# alt.net
KiCad netlist of a schematic drawn in EAGLE
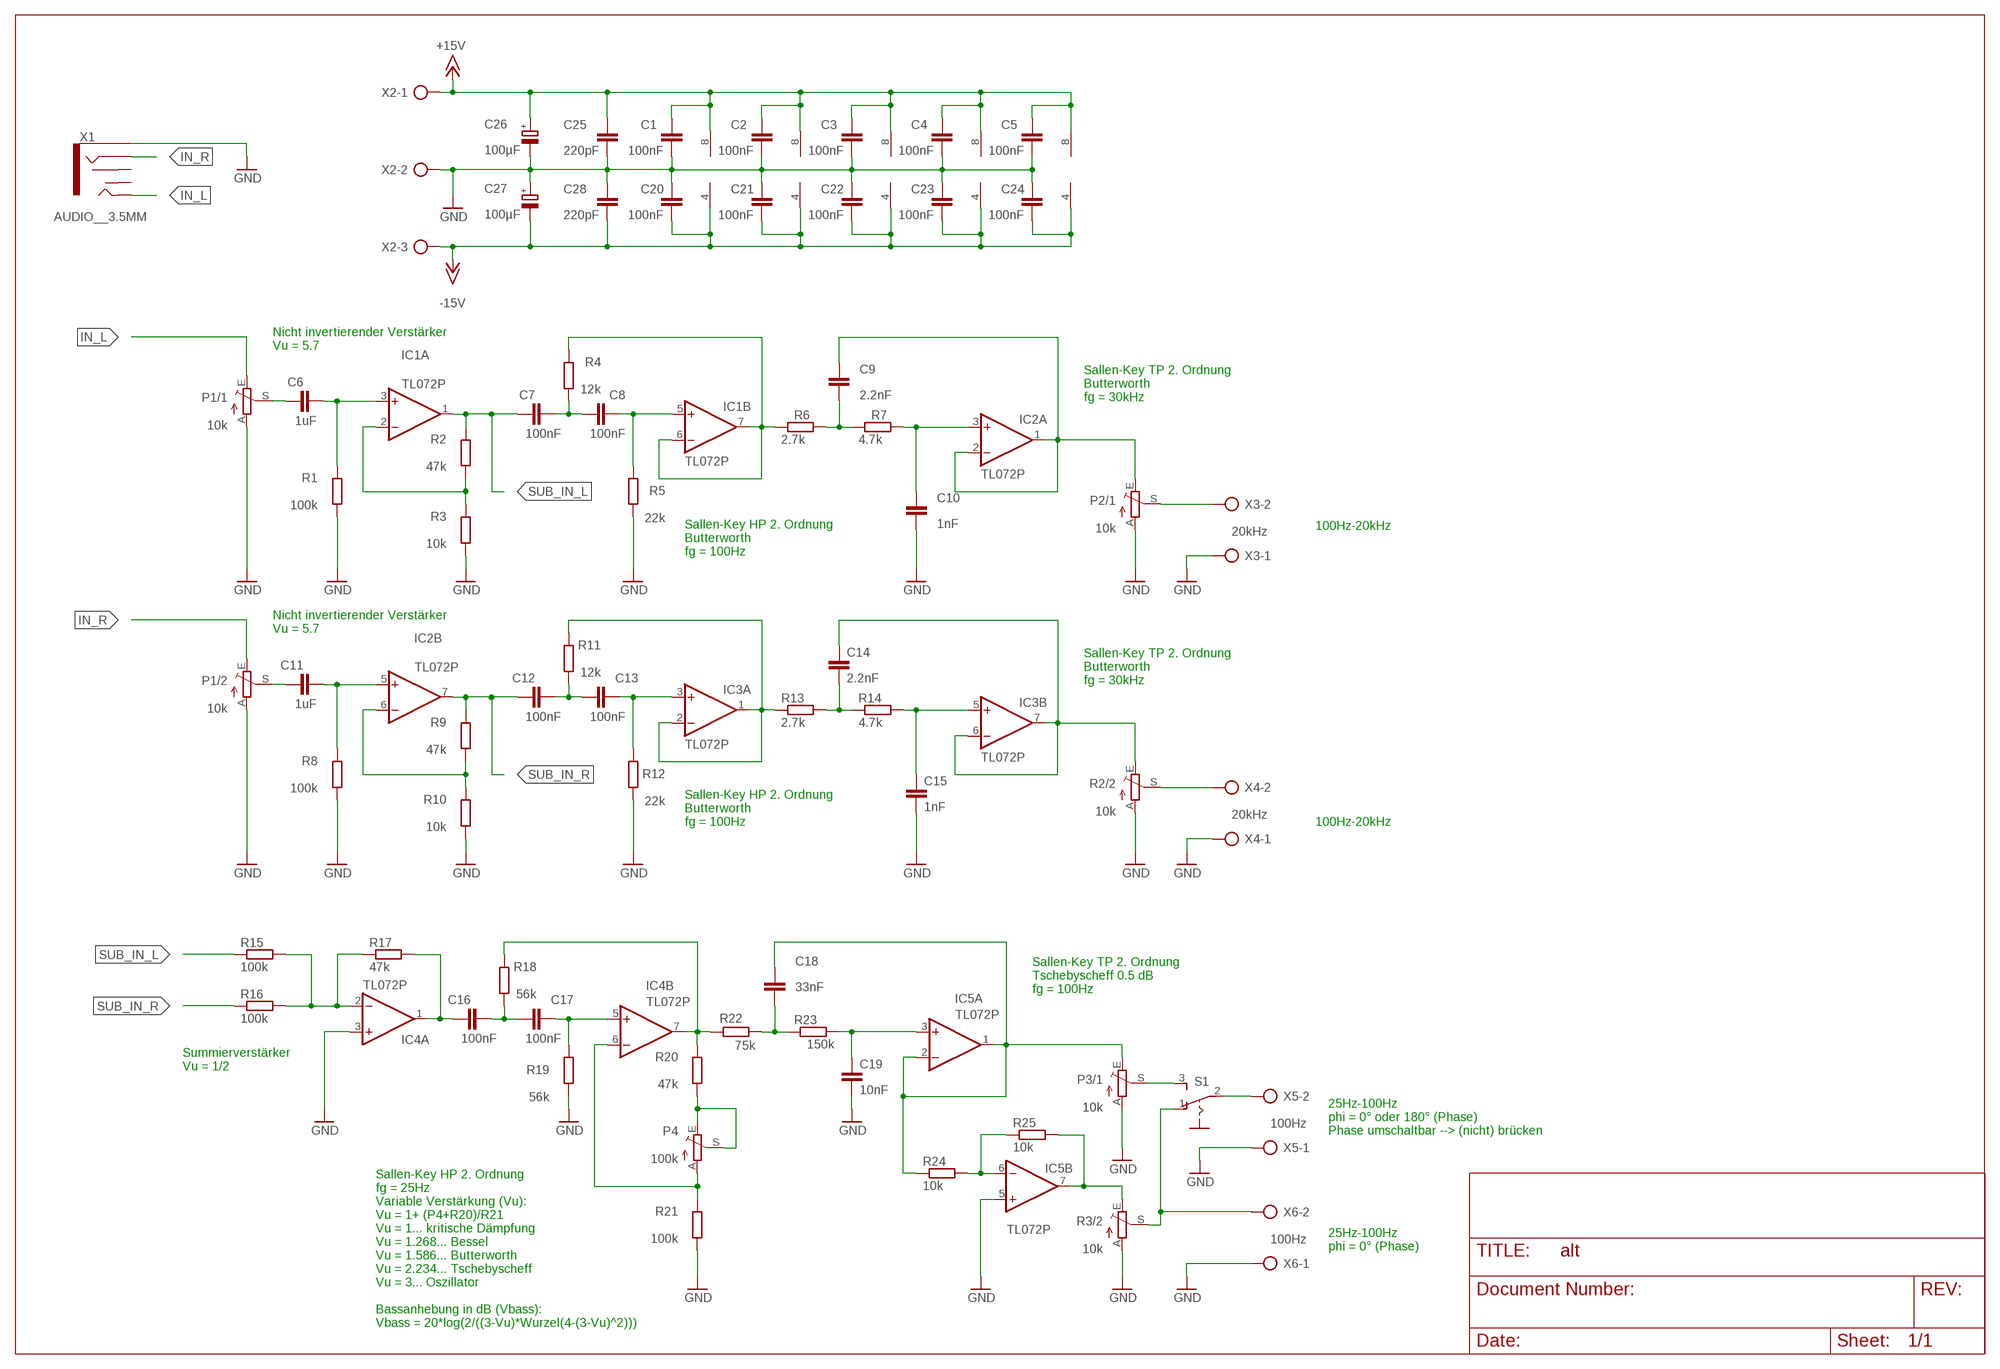
[diagram p0: schematic, sheet 1]

(export (version "E")
  (design (tool "Eeschema 10.0.6"))
  (components
    (comp (ref "C1")
      (value "100nF")
      (footprint "eagle-import:C025-025X050")
      (libsource (lib "eagle-import") (part "C-EU025-025X050"))
    )
    (comp (ref "C2")
      (value "100nF")
      (footprint "eagle-import:C025-025X050")
      (libsource (lib "eagle-import") (part "C-EU025-025X050"))
    )
    (comp (ref "C3")
      (value "100nF")
      (footprint "eagle-import:C025-025X050")
      (libsource (lib "eagle-import") (part "C-EU025-025X050"))
    )
    (comp (ref "C4")
      (value "100nF")
      (footprint "eagle-import:C025-025X050")
      (libsource (lib "eagle-import") (part "C-EU025-025X050"))
    )
    (comp (ref "C5")
      (value "100nF")
      (footprint "eagle-import:C025-025X050")
      (libsource (lib "eagle-import") (part "C-EU025-025X050"))
    )
    (comp (ref "C6")
      (value "1uF")
      (footprint "eagle-import:C025-025X050")
      (libsource (lib "eagle-import") (part "resistor_C-EU025-025X050"))
    )
    (comp (ref "C7")
      (value "100nF")
      (footprint "eagle-import:C025-025X050")
      (libsource (lib "eagle-import") (part "resistor_C-EU025-025X050"))
    )
    (comp (ref "C8")
      (value "100nF")
      (footprint "eagle-import:C025-025X050")
      (libsource (lib "eagle-import") (part "resistor_C-EU025-025X050"))
    )
    (comp (ref "C9")
      (value "2.2nF")
      (footprint "eagle-import:C025-025X050")
      (libsource (lib "eagle-import") (part "resistor_C-EU025-025X050"))
    )
    (comp (ref "C10")
      (value "1nF")
      (footprint "eagle-import:C025-025X050")
      (libsource (lib "eagle-import") (part "resistor_C-EU025-025X050"))
    )
    (comp (ref "C11")
      (value "1uF")
      (footprint "eagle-import:C025-025X050")
      (libsource (lib "eagle-import") (part "resistor_C-EU025-025X050"))
    )
    (comp (ref "C12")
      (value "100nF")
      (footprint "eagle-import:C025-025X050")
      (libsource (lib "eagle-import") (part "resistor_C-EU025-025X050"))
    )
    (comp (ref "C13")
      (value "100nF")
      (footprint "eagle-import:C025-025X050")
      (libsource (lib "eagle-import") (part "resistor_C-EU025-025X050"))
    )
    (comp (ref "C14")
      (value "2.2nF")
      (footprint "eagle-import:C025-025X050")
      (libsource (lib "eagle-import") (part "resistor_C-EU025-025X050"))
    )
    (comp (ref "C15")
      (value "1nF")
      (footprint "eagle-import:C025-025X050")
      (libsource (lib "eagle-import") (part "resistor_C-EU025-025X050"))
    )
    (comp (ref "C16")
      (value "100nF")
      (footprint "eagle-import:C050-025X075")
      (libsource (lib "eagle-import") (part "C-EU050-025X075"))
    )
    (comp (ref "C17")
      (value "100nF")
      (footprint "eagle-import:C025-025X050")
      (libsource (lib "eagle-import") (part "C-EU025-025X050"))
    )
    (comp (ref "C18")
      (value "33nF")
      (footprint "eagle-import:C025-025X050")
      (libsource (lib "eagle-import") (part "C-EU025-025X050"))
    )
    (comp (ref "C19")
      (value "10nF")
      (footprint "eagle-import:C025-025X050")
      (libsource (lib "eagle-import") (part "C-EU025-025X050"))
    )
    (comp (ref "C20")
      (value "100nF")
      (footprint "eagle-import:C025-025X050")
      (libsource (lib "eagle-import") (part "C-EU025-025X050"))
    )
    (comp (ref "C21")
      (value "100nF")
      (footprint "eagle-import:C025-025X050")
      (libsource (lib "eagle-import") (part "C-EU025-025X050"))
    )
    (comp (ref "C22")
      (value "100nF")
      (footprint "eagle-import:C025-025X050")
      (libsource (lib "eagle-import") (part "C-EU025-025X050"))
    )
    (comp (ref "C23")
      (value "100nF")
      (footprint "eagle-import:C025-025X050")
      (libsource (lib "eagle-import") (part "C-EU025-025X050"))
    )
    (comp (ref "C24")
      (value "100nF")
      (footprint "eagle-import:C025-025X050")
      (libsource (lib "eagle-import") (part "C-EU025-025X050"))
    )
    (comp (ref "C25")
      (value "220pF")
      (footprint "eagle-import:C025-025X050")
      (libsource (lib "eagle-import") (part "C-EU025-025X050"))
    )
    (comp (ref "C26")
      (value "100µF")
      (footprint "eagle-import:E2,5-6")
      (libsource (lib "eagle-import") (part "CPOL-EUE2.5-6"))
    )
    (comp (ref "C27")
      (value "100µF")
      (footprint "eagle-import:E2,5-6")
      (libsource (lib "eagle-import") (part "CPOL-EUE2.5-6"))
    )
    (comp (ref "C28")
      (value "220pF")
      (footprint "eagle-import:C025-025X050")
      (libsource (lib "eagle-import") (part "C-EU025-025X050"))
    )
    (comp (ref "IC1")
      (value "TL072P")
      (footprint "eagle-import:DIL08")
      (libsource (lib "eagle-import") (part "TL072P"))
    )
    (comp (ref "IC2")
      (value "TL072P")
      (footprint "eagle-import:DIL08")
      (libsource (lib "eagle-import") (part "TL072P"))
    )
    (comp (ref "IC3")
      (value "TL072P")
      (footprint "eagle-import:DIL08")
      (libsource (lib "eagle-import") (part "TL072P"))
    )
    (comp (ref "IC4")
      (value "TL072P")
      (footprint "eagle-import:DIL08")
      (libsource (lib "eagle-import") (part "TL072P"))
    )
    (comp (ref "IC5")
      (value "TL072P")
      (footprint "eagle-import:DIL08")
      (libsource (lib "eagle-import") (part "TL072P"))
    )
    (comp (ref "P1/1")
      (value "10k")
      (footprint "eagle-import:B64Y")
      (libsource (lib "eagle-import") (part "TRIM_EU-B64Y"))
    )
    (comp (ref "P1/2")
      (value "10k")
      (footprint "eagle-import:B64Y")
      (libsource (lib "eagle-import") (part "TRIM_EU-B64Y"))
    )
    (comp (ref "P2/1")
      (value "10k")
      (footprint "eagle-import:B64Y")
      (libsource (lib "eagle-import") (part "TRIM_EU-B64Y"))
    )
    (comp (ref "P3/1")
      (value "10k")
      (footprint "eagle-import:B64Y")
      (libsource (lib "eagle-import") (part "TRIM_EU-B64Y"))
    )
    (comp (ref "P4")
      (value "100k")
      (footprint "eagle-import:B64Y")
      (libsource (lib "eagle-import") (part "TRIM_EU-B64Y"))
    )
    (comp (ref "R1")
      (value "100k")
      (footprint "eagle-import:0207_10")
      (libsource (lib "eagle-import") (part "resistor_R-EU_0207/10"))
    )
    (comp (ref "R2")
      (value "47k")
      (footprint "eagle-import:0207_10")
      (libsource (lib "eagle-import") (part "resistor_R-EU_0207/10"))
    )
    (comp (ref "R2/2")
      (value "10k")
      (footprint "eagle-import:B64Y")
      (libsource (lib "eagle-import") (part "TRIM_EU-B64Y"))
    )
    (comp (ref "R3")
      (value "10k")
      (footprint "eagle-import:0207_10")
      (libsource (lib "eagle-import") (part "resistor_R-EU_0207/10"))
    )
    (comp (ref "R3/2")
      (value "10k")
      (footprint "eagle-import:B64Y")
      (libsource (lib "eagle-import") (part "TRIM_EU-B64Y"))
    )
    (comp (ref "R4")
      (value "12k")
      (footprint "eagle-import:0207_10")
      (libsource (lib "eagle-import") (part "resistor_R-EU_0207/10"))
    )
    (comp (ref "R5")
      (value "22k")
      (footprint "eagle-import:0207_10")
      (libsource (lib "eagle-import") (part "resistor_R-EU_0207/10"))
    )
    (comp (ref "R6")
      (value "2.7k")
      (footprint "eagle-import:0207_10")
      (libsource (lib "eagle-import") (part "resistor_R-EU_0207/10"))
    )
    (comp (ref "R7")
      (value "4.7k")
      (footprint "eagle-import:0207_10")
      (libsource (lib "eagle-import") (part "resistor_R-EU_0207/10"))
    )
    (comp (ref "R8")
      (value "100k")
      (footprint "eagle-import:0207_7")
      (libsource (lib "eagle-import") (part "R-EU_0207/7"))
    )
    (comp (ref "R9")
      (value "47k")
      (footprint "eagle-import:0207_7")
      (libsource (lib "eagle-import") (part "R-EU_0207/7"))
    )
    (comp (ref "R10")
      (value "10k")
      (footprint "eagle-import:0207_10")
      (libsource (lib "eagle-import") (part "resistor_R-EU_0207/10"))
    )
    (comp (ref "R11")
      (value "12k")
      (footprint "eagle-import:0207_10")
      (libsource (lib "eagle-import") (part "resistor_R-EU_0207/10"))
    )
    (comp (ref "R12")
      (value "22k")
      (footprint "eagle-import:0207_10")
      (libsource (lib "eagle-import") (part "resistor_R-EU_0207/10"))
    )
    (comp (ref "R13")
      (value "2.7k")
      (footprint "eagle-import:0207_10")
      (libsource (lib "eagle-import") (part "resistor_R-EU_0207/10"))
    )
    (comp (ref "R14")
      (value "4.7k")
      (footprint "eagle-import:0207_10")
      (libsource (lib "eagle-import") (part "resistor_R-EU_0207/10"))
    )
    (comp (ref "R15")
      (value "100k")
      (footprint "eagle-import:0207_10")
      (libsource (lib "eagle-import") (part "R-EU_0207/10"))
    )
    (comp (ref "R16")
      (value "100k")
      (footprint "eagle-import:0207_10")
      (libsource (lib "eagle-import") (part "R-EU_0207/10"))
    )
    (comp (ref "R17")
      (value "47k")
      (footprint "eagle-import:0207_10")
      (libsource (lib "eagle-import") (part "R-EU_0207/10"))
    )
    (comp (ref "R18")
      (value "56k")
      (footprint "eagle-import:0207_10")
      (libsource (lib "eagle-import") (part "R-EU_0207/10"))
    )
    (comp (ref "R19")
      (value "56k")
      (footprint "eagle-import:0207_7")
      (libsource (lib "eagle-import") (part "R-EU_0207/7"))
    )
    (comp (ref "R20")
      (value "47k")
      (footprint "eagle-import:0207_10")
      (libsource (lib "eagle-import") (part "R-EU_0207/10"))
    )
    (comp (ref "R21")
      (value "100k")
      (footprint "eagle-import:0207_10")
      (libsource (lib "eagle-import") (part "R-EU_0207/10"))
    )
    (comp (ref "R22")
      (value "75k")
      (footprint "eagle-import:0207_7")
      (libsource (lib "eagle-import") (part "R-EU_0207/7"))
    )
    (comp (ref "R23")
      (value "150k")
      (footprint "eagle-import:0207_10")
      (libsource (lib "eagle-import") (part "R-EU_0207/10"))
    )
    (comp (ref "R24")
      (value "10k")
      (footprint "eagle-import:0207_10")
      (libsource (lib "eagle-import") (part "R-EU_0207/10"))
    )
    (comp (ref "R25")
      (value "10k")
      (footprint "eagle-import:0207_10")
      (libsource (lib "eagle-import") (part "R-EU_0207/10"))
    )
    (comp (ref "S1")
      (value "255SB")
      (footprint "eagle-import:255SB")
      (libsource (lib "eagle-import") (part "255SB"))
    )
    (comp (ref "X1")
      (value "AUDIO__3.5MM")
      (footprint "eagle-import:AUDIO-JACK")
      (libsource (lib "eagle-import") (part "AUDIO_JACK_3.5MM_PTH"))
    )
    (comp (ref "X2")
      (value "AK300/3")
      (footprint "eagle-import:AK300_3")
      (libsource (lib "eagle-import") (part "AK300/3"))
    )
    (comp (ref "X3")
      (value "20kHz")
      (footprint "eagle-import:AK300_2")
      (libsource (lib "eagle-import") (part "AK300/2"))
    )
    (comp (ref "X4")
      (value "20kHz")
      (footprint "eagle-import:AK300_2")
      (libsource (lib "eagle-import") (part "AK300/2"))
    )
    (comp (ref "X5")
      (value "100Hz")
      (footprint "eagle-import:AK300_2")
      (libsource (lib "eagle-import") (part "AK300/2"))
    )
    (comp (ref "X6")
      (value "100Hz")
      (footprint "eagle-import:AK300_2")
      (libsource (lib "eagle-import") (part "AK300/2"))
    )
  )
  (nets
    (net (code "1") (name "+15V") (class "Default")
      (node (ref "C1") (pin "1") (pinfunction "1_1") (pintype "passive"))
      (node (ref "C2") (pin "1") (pinfunction "1_1") (pintype "passive"))
      (node (ref "C25") (pin "1") (pinfunction "1_1") (pintype "passive"))
      (node (ref "C26") (pin "+") (pinfunction "+_+") (pintype "passive"))
      (node (ref "C3") (pin "1") (pinfunction "1_1") (pintype "passive"))
      (node (ref "C4") (pin "1") (pinfunction "1_1") (pintype "passive"))
      (node (ref "C5") (pin "1") (pinfunction "1_1") (pintype "passive"))
      (node (ref "IC1") (pin "8") (pinfunction "V+_8") (pintype "power_in"))
      (node (ref "IC2") (pin "8") (pinfunction "V+_8") (pintype "power_in"))
      (node (ref "IC3") (pin "8") (pinfunction "V+_8") (pintype "power_in"))
      (node (ref "IC4") (pin "8") (pinfunction "V+_8") (pintype "power_in"))
      (node (ref "IC5") (pin "8") (pinfunction "V+_8") (pintype "power_in"))
      (node (ref "X2") (pin "1") (pinfunction "KL_1") (pintype "passive"))
    )
    (net (code "2") (name "-15V") (class "Default")
      (node (ref "C20") (pin "2") (pinfunction "2_2") (pintype "passive"))
      (node (ref "C21") (pin "2") (pinfunction "2_2") (pintype "passive"))
      (node (ref "C22") (pin "2") (pinfunction "2_2") (pintype "passive"))
      (node (ref "C23") (pin "2") (pinfunction "2_2") (pintype "passive"))
      (node (ref "C24") (pin "2") (pinfunction "2_2") (pintype "passive"))
      (node (ref "C27") (pin "-") (pinfunction "-_-") (pintype "passive"))
      (node (ref "C28") (pin "2") (pinfunction "2_2") (pintype "passive"))
      (node (ref "IC1") (pin "4") (pinfunction "V-_4") (pintype "power_in"))
      (node (ref "IC2") (pin "4") (pinfunction "V-_4") (pintype "power_in"))
      (node (ref "IC3") (pin "4") (pinfunction "V-_4") (pintype "power_in"))
      (node (ref "IC4") (pin "4") (pinfunction "V-_4") (pintype "power_in"))
      (node (ref "IC5") (pin "4") (pinfunction "V-_4") (pintype "power_in"))
      (node (ref "X2") (pin "3") (pinfunction "KL_3") (pintype "passive"))
    )
    (net (code "3") (name "GND") (class "Default")
      (node (ref "C1") (pin "2") (pinfunction "2_2") (pintype "passive"))
      (node (ref "C10") (pin "2") (pinfunction "2_2") (pintype "passive"))
      (node (ref "C15") (pin "2") (pinfunction "2_2") (pintype "passive"))
      (node (ref "C19") (pin "2") (pinfunction "2_2") (pintype "passive"))
      (node (ref "C2") (pin "2") (pinfunction "2_2") (pintype "passive"))
      (node (ref "C20") (pin "1") (pinfunction "1_1") (pintype "passive"))
      (node (ref "C21") (pin "1") (pinfunction "1_1") (pintype "passive"))
      (node (ref "C22") (pin "1") (pinfunction "1_1") (pintype "passive"))
      (node (ref "C23") (pin "1") (pinfunction "1_1") (pintype "passive"))
      (node (ref "C24") (pin "1") (pinfunction "1_1") (pintype "passive"))
      (node (ref "C25") (pin "2") (pinfunction "2_2") (pintype "passive"))
      (node (ref "C26") (pin "-") (pinfunction "-_-") (pintype "passive"))
      (node (ref "C27") (pin "+") (pinfunction "+_+") (pintype "passive"))
      (node (ref "C28") (pin "1") (pinfunction "1_1") (pintype "passive"))
      (node (ref "C3") (pin "2") (pinfunction "2_2") (pintype "passive"))
      (node (ref "C4") (pin "2") (pinfunction "2_2") (pintype "passive"))
      (node (ref "C5") (pin "2") (pinfunction "2_2") (pintype "passive"))
      (node (ref "IC4") (pin "3") (pinfunction "+IN_3") (pintype "input"))
      (node (ref "IC5") (pin "5") (pinfunction "+IN_5") (pintype "input"))
      (node (ref "P1/1") (pin "A") (pinfunction "A_A") (pintype "passive"))
      (node (ref "P1/2") (pin "A") (pinfunction "A_A") (pintype "passive"))
      (node (ref "P2/1") (pin "A") (pinfunction "A_A") (pintype "passive"))
      (node (ref "P3/1") (pin "A") (pinfunction "A_A") (pintype "passive"))
      (node (ref "R1") (pin "1") (pinfunction "1_1") (pintype "passive"))
      (node (ref "R10") (pin "1") (pinfunction "1_1") (pintype "passive"))
      (node (ref "R12") (pin "1") (pinfunction "1_1") (pintype "passive"))
      (node (ref "R19") (pin "1") (pinfunction "1_1") (pintype "passive"))
      (node (ref "R2/2") (pin "A") (pinfunction "A_A") (pintype "passive"))
      (node (ref "R21") (pin "1") (pinfunction "1_1") (pintype "passive"))
      (node (ref "R3") (pin "1") (pinfunction "1_1") (pintype "passive"))
      (node (ref "R3/2") (pin "A") (pinfunction "A_A") (pintype "passive"))
      (node (ref "R5") (pin "1") (pinfunction "1_1") (pintype "passive"))
      (node (ref "R8") (pin "1") (pinfunction "1_1") (pintype "passive"))
      (node (ref "X1") (pin "SLEEVE") (pinfunction "SLEEVE_SLEEVE") (pintype "bidirectional"))
      (node (ref "X2") (pin "2") (pinfunction "KL_2") (pintype "passive"))
      (node (ref "X3") (pin "1") (pinfunction "KL_1") (pintype "passive"))
      (node (ref "X4") (pin "1") (pinfunction "KL_1") (pintype "passive"))
      (node (ref "X5") (pin "1") (pinfunction "KL_1") (pintype "passive"))
      (node (ref "X6") (pin "1") (pinfunction "KL_1") (pintype "passive"))
    )
    (net (code "4") (name "IN_L") (class "Default")
      (node (ref "P1/1") (pin "E") (pinfunction "E_E") (pintype "passive"))
      (node (ref "X1") (pin "TIP") (pinfunction "TIP_TIP") (pintype "bidirectional"))
    )
    (net (code "5") (name "IN_R") (class "Default")
      (node (ref "P1/2") (pin "E") (pinfunction "E_E") (pintype "passive"))
      (node (ref "X1") (pin "RING") (pinfunction "RING_RING") (pintype "bidirectional"))
    )
    (net (code "6") (name "Net-(C6-Pad1)") (class "Default")
      (node (ref "C6") (pin "1") (pinfunction "1_1") (pintype "passive"))
      (node (ref "P1/1") (pin "S") (pinfunction "S_S") (pintype "passive"))
    )
    (net (code "7") (name "Net-(C7-Pad2)") (class "Default")
      (node (ref "C7") (pin "2") (pinfunction "2_2") (pintype "passive"))
      (node (ref "C8") (pin "1") (pinfunction "1_1") (pintype "passive"))
      (node (ref "R4") (pin "1") (pinfunction "1_1") (pintype "passive"))
    )
    (net (code "8") (name "Net-(C9-Pad2)") (class "Default")
      (node (ref "C9") (pin "2") (pinfunction "2_2") (pintype "passive"))
      (node (ref "R6") (pin "2") (pinfunction "2_2") (pintype "passive"))
      (node (ref "R7") (pin "1") (pinfunction "1_1") (pintype "passive"))
    )
    (net (code "9") (name "Net-(C11-Pad1)") (class "Default")
      (node (ref "C11") (pin "1") (pinfunction "1_1") (pintype "passive"))
      (node (ref "P1/2") (pin "S") (pinfunction "S_S") (pintype "passive"))
    )
    (net (code "10") (name "Net-(C12-Pad2)") (class "Default")
      (node (ref "C12") (pin "2") (pinfunction "2_2") (pintype "passive"))
      (node (ref "C13") (pin "1") (pinfunction "1_1") (pintype "passive"))
      (node (ref "R11") (pin "1") (pinfunction "1_1") (pintype "passive"))
    )
    (net (code "11") (name "Net-(C14-Pad2)") (class "Default")
      (node (ref "C14") (pin "2") (pinfunction "2_2") (pintype "passive"))
      (node (ref "R13") (pin "2") (pinfunction "2_2") (pintype "passive"))
      (node (ref "R14") (pin "1") (pinfunction "1_1") (pintype "passive"))
    )
    (net (code "12") (name "Net-(C16-Pad2)") (class "Default")
      (node (ref "C16") (pin "2") (pinfunction "2_2") (pintype "passive"))
      (node (ref "C17") (pin "1") (pinfunction "1_1") (pintype "passive"))
      (node (ref "R18") (pin "1") (pinfunction "1_1") (pintype "passive"))
    )
    (net (code "13") (name "Net-(C18-Pad2)") (class "Default")
      (node (ref "C18") (pin "2") (pinfunction "2_2") (pintype "passive"))
      (node (ref "R22") (pin "1") (pinfunction "1_1") (pintype "passive"))
      (node (ref "R23") (pin "1") (pinfunction "1_1") (pintype "passive"))
    )
    (net (code "14") (name "Net-(IC1A-+IN)") (class "Default")
      (node (ref "C6") (pin "2") (pinfunction "2_2") (pintype "passive"))
      (node (ref "IC1") (pin "3") (pinfunction "+IN_3") (pintype "input"))
      (node (ref "R1") (pin "2") (pinfunction "2_2") (pintype "passive"))
    )
    (net (code "15") (name "Net-(IC1A--IN)") (class "Default")
      (node (ref "IC1") (pin "2") (pinfunction "-IN_2") (pintype "input"))
      (node (ref "R2") (pin "1") (pinfunction "1_1") (pintype "passive"))
      (node (ref "R3") (pin "2") (pinfunction "2_2") (pintype "passive"))
    )
    (net (code "16") (name "Net-(IC1B-+IN)") (class "Default")
      (node (ref "C8") (pin "2") (pinfunction "2_2") (pintype "passive"))
      (node (ref "IC1") (pin "5") (pinfunction "+IN_5") (pintype "input"))
      (node (ref "R5") (pin "2") (pinfunction "2_2") (pintype "passive"))
    )
    (net (code "17") (name "Net-(IC1B--IN)") (class "Default")
      (node (ref "IC1") (pin "6") (pinfunction "-IN_6") (pintype "input"))
      (node (ref "IC1") (pin "7") (pinfunction "OUT_7") (pintype "output"))
      (node (ref "R4") (pin "2") (pinfunction "2_2") (pintype "passive"))
      (node (ref "R6") (pin "1") (pinfunction "1_1") (pintype "passive"))
    )
    (net (code "18") (name "Net-(IC2A-+IN)") (class "Default")
      (node (ref "C10") (pin "1") (pinfunction "1_1") (pintype "passive"))
      (node (ref "IC2") (pin "3") (pinfunction "+IN_3") (pintype "input"))
      (node (ref "R7") (pin "2") (pinfunction "2_2") (pintype "passive"))
    )
    (net (code "19") (name "Net-(IC2A--IN)") (class "Default")
      (node (ref "C9") (pin "1") (pinfunction "1_1") (pintype "passive"))
      (node (ref "IC2") (pin "1") (pinfunction "OUT_1") (pintype "output"))
      (node (ref "IC2") (pin "2") (pinfunction "-IN_2") (pintype "input"))
      (node (ref "P2/1") (pin "E") (pinfunction "E_E") (pintype "passive"))
    )
    (net (code "20") (name "Net-(IC2B-+IN)") (class "Default")
      (node (ref "C11") (pin "2") (pinfunction "2_2") (pintype "passive"))
      (node (ref "IC2") (pin "5") (pinfunction "+IN_5") (pintype "input"))
      (node (ref "R8") (pin "2") (pinfunction "2_2") (pintype "passive"))
    )
    (net (code "21") (name "Net-(IC2B--IN)") (class "Default")
      (node (ref "IC2") (pin "6") (pinfunction "-IN_6") (pintype "input"))
      (node (ref "R10") (pin "2") (pinfunction "2_2") (pintype "passive"))
      (node (ref "R9") (pin "1") (pinfunction "1_1") (pintype "passive"))
    )
    (net (code "22") (name "Net-(IC3A-+IN)") (class "Default")
      (node (ref "C13") (pin "2") (pinfunction "2_2") (pintype "passive"))
      (node (ref "IC3") (pin "3") (pinfunction "+IN_3") (pintype "input"))
      (node (ref "R12") (pin "2") (pinfunction "2_2") (pintype "passive"))
    )
    (net (code "23") (name "Net-(IC3A--IN)") (class "Default")
      (node (ref "IC3") (pin "1") (pinfunction "OUT_1") (pintype "output"))
      (node (ref "IC3") (pin "2") (pinfunction "-IN_2") (pintype "input"))
      (node (ref "R11") (pin "2") (pinfunction "2_2") (pintype "passive"))
      (node (ref "R13") (pin "1") (pinfunction "1_1") (pintype "passive"))
    )
    (net (code "24") (name "Net-(IC3B-+IN)") (class "Default")
      (node (ref "C15") (pin "1") (pinfunction "1_1") (pintype "passive"))
      (node (ref "IC3") (pin "5") (pinfunction "+IN_5") (pintype "input"))
      (node (ref "R14") (pin "2") (pinfunction "2_2") (pintype "passive"))
    )
    (net (code "25") (name "Net-(IC3B--IN)") (class "Default")
      (node (ref "C14") (pin "1") (pinfunction "1_1") (pintype "passive"))
      (node (ref "IC3") (pin "6") (pinfunction "-IN_6") (pintype "input"))
      (node (ref "IC3") (pin "7") (pinfunction "OUT_7") (pintype "output"))
      (node (ref "R2/2") (pin "E") (pinfunction "E_E") (pintype "passive"))
    )
    (net (code "26") (name "Net-(IC4A--IN)") (class "Default")
      (node (ref "IC4") (pin "2") (pinfunction "-IN_2") (pintype "input"))
      (node (ref "R15") (pin "2") (pinfunction "2_2") (pintype "passive"))
      (node (ref "R16") (pin "2") (pinfunction "2_2") (pintype "passive"))
      (node (ref "R17") (pin "1") (pinfunction "1_1") (pintype "passive"))
    )
    (net (code "27") (name "Net-(IC4A-OUT)") (class "Default")
      (node (ref "C16") (pin "1") (pinfunction "1_1") (pintype "passive"))
      (node (ref "IC4") (pin "1") (pinfunction "OUT_1") (pintype "output"))
      (node (ref "R17") (pin "2") (pinfunction "2_2") (pintype "passive"))
    )
    (net (code "28") (name "Net-(IC4B-+IN)") (class "Default")
      (node (ref "C17") (pin "2") (pinfunction "2_2") (pintype "passive"))
      (node (ref "IC4") (pin "5") (pinfunction "+IN_5") (pintype "input"))
      (node (ref "R19") (pin "2") (pinfunction "2_2") (pintype "passive"))
    )
    (net (code "29") (name "Net-(IC4B--IN)") (class "Default")
      (node (ref "IC4") (pin "6") (pinfunction "-IN_6") (pintype "input"))
      (node (ref "P4") (pin "A") (pinfunction "A_A") (pintype "passive"))
      (node (ref "R21") (pin "2") (pinfunction "2_2") (pintype "passive"))
    )
    (net (code "30") (name "Net-(IC4B-OUT)") (class "Default")
      (node (ref "IC4") (pin "7") (pinfunction "OUT_7") (pintype "output"))
      (node (ref "R18") (pin "2") (pinfunction "2_2") (pintype "passive"))
      (node (ref "R20") (pin "2") (pinfunction "2_2") (pintype "passive"))
      (node (ref "R22") (pin "2") (pinfunction "2_2") (pintype "passive"))
    )
    (net (code "31") (name "Net-(IC5A-+IN)") (class "Default")
      (node (ref "C19") (pin "1") (pinfunction "1_1") (pintype "passive"))
      (node (ref "IC5") (pin "3") (pinfunction "+IN_3") (pintype "input"))
      (node (ref "R23") (pin "2") (pinfunction "2_2") (pintype "passive"))
    )
    (net (code "32") (name "Net-(IC5A--IN)") (class "Default")
      (node (ref "C18") (pin "1") (pinfunction "1_1") (pintype "passive"))
      (node (ref "IC5") (pin "1") (pinfunction "OUT_1") (pintype "output"))
      (node (ref "IC5") (pin "2") (pinfunction "-IN_2") (pintype "input"))
      (node (ref "P3/1") (pin "E") (pinfunction "E_E") (pintype "passive"))
      (node (ref "R24") (pin "1") (pinfunction "1_1") (pintype "passive"))
    )
    (net (code "33") (name "Net-(IC5B--IN)") (class "Default")
      (node (ref "IC5") (pin "6") (pinfunction "-IN_6") (pintype "input"))
      (node (ref "R24") (pin "2") (pinfunction "2_2") (pintype "passive"))
      (node (ref "R25") (pin "1") (pinfunction "1_1") (pintype "passive"))
    )
    (net (code "34") (name "Net-(IC5B-OUT)") (class "Default")
      (node (ref "IC5") (pin "7") (pinfunction "OUT_7") (pintype "output"))
      (node (ref "R25") (pin "2") (pinfunction "2_2") (pintype "passive"))
      (node (ref "R3/2") (pin "E") (pinfunction "E_E") (pintype "passive"))
    )
    (net (code "35") (name "Net-(P4-PadE)") (class "Default")
      (node (ref "P4") (pin "E") (pinfunction "E_E") (pintype "passive"))
      (node (ref "P4") (pin "S") (pinfunction "S_S") (pintype "passive"))
      (node (ref "R20") (pin "1") (pinfunction "1_1") (pintype "passive"))
    )
    (net (code "36") (name "Net-(S1-O)") (class "Default")
      (node (ref "R3/2") (pin "S") (pinfunction "S_S") (pintype "passive"))
      (node (ref "S1") (pin "1") (pinfunction "O_1") (pintype "passive"))
      (node (ref "X6") (pin "2") (pinfunction "KL_2") (pintype "passive"))
    )
    (net (code "37") (name "Net-(S1-P)") (class "Default")
      (node (ref "S1") (pin "2") (pinfunction "P_2") (pintype "passive"))
      (node (ref "X5") (pin "2") (pinfunction "KL_2") (pintype "passive"))
    )
    (net (code "38") (name "Net-(S1-S)") (class "Default")
      (node (ref "P3/1") (pin "S") (pinfunction "S_S") (pintype "passive"))
      (node (ref "S1") (pin "3") (pinfunction "S_3") (pintype "passive"))
    )
    (net (code "39") (name "Net-(X3B-KL)") (class "Default")
      (node (ref "P2/1") (pin "S") (pinfunction "S_S") (pintype "passive"))
      (node (ref "X3") (pin "2") (pinfunction "KL_2") (pintype "passive"))
    )
    (net (code "40") (name "Net-(X4B-KL)") (class "Default")
      (node (ref "R2/2") (pin "S") (pinfunction "S_S") (pintype "passive"))
      (node (ref "X4") (pin "2") (pinfunction "KL_2") (pintype "passive"))
    )
    (net (code "41") (name "SUB_IN_L") (class "Default")
      (node (ref "C7") (pin "1") (pinfunction "1_1") (pintype "passive"))
      (node (ref "IC1") (pin "1") (pinfunction "OUT_1") (pintype "output"))
      (node (ref "R15") (pin "1") (pinfunction "1_1") (pintype "passive"))
      (node (ref "R2") (pin "2") (pinfunction "2_2") (pintype "passive"))
    )
    (net (code "42") (name "SUB_IN_R") (class "Default")
      (node (ref "C12") (pin "1") (pinfunction "1_1") (pintype "passive"))
      (node (ref "IC2") (pin "7") (pinfunction "OUT_7") (pintype "output"))
      (node (ref "R16") (pin "1") (pinfunction "1_1") (pintype "passive"))
      (node (ref "R9") (pin "2") (pinfunction "2_2") (pintype "passive"))
    )
    (net (code "43") (name "unconnected-(X1-PadRSH)") (class "Default")
      (node (ref "X1") (pin "RSH") (pinfunction "RSH_RSH") (pintype "bidirectional"))
    )
    (net (code "44") (name "unconnected-(X1-PadTSH)") (class "Default")
      (node (ref "X1") (pin "TSH") (pinfunction "TSH_TSH") (pintype "bidirectional"))
    )
  )
)
